# EFR32BG13_EF_Antenna_Power.net
KiCad netlist of a schematic drawn in Altium Designer
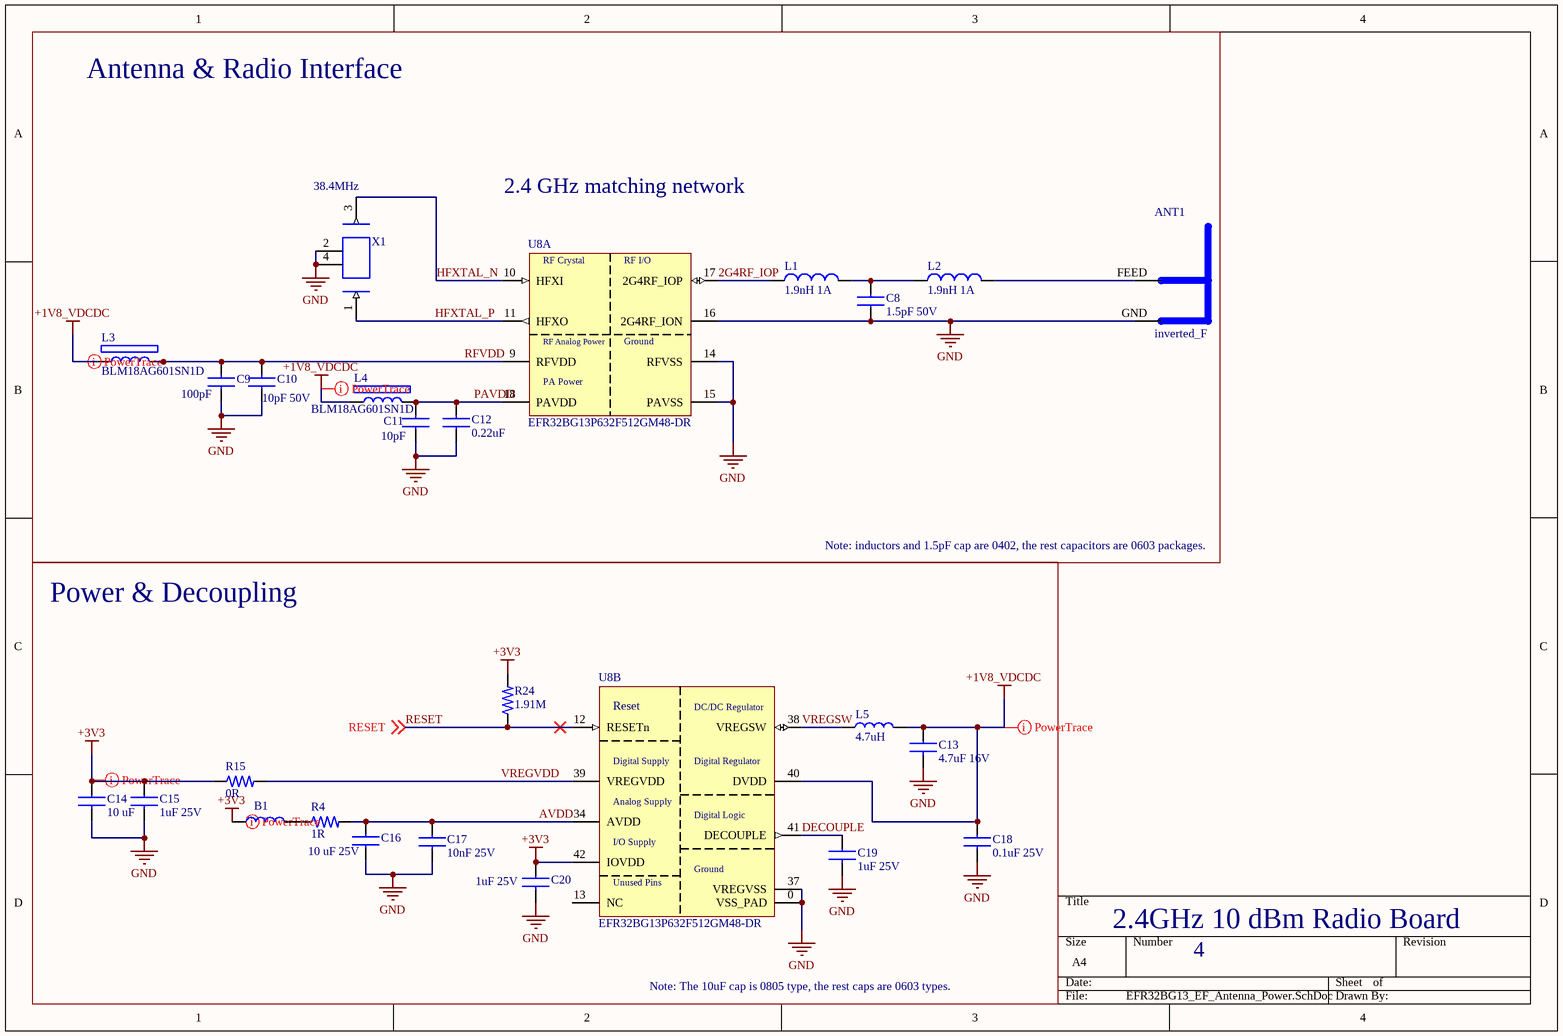
[diagram p0: EFR32BG13_EF_Antenna_Power.SchDoc]

(export (version "E")
  (design (tool "Eeschema 10.0.6"))
  (components
    (comp (ref "ANT1")
      (value "inverted_F")
      (footprint "Inverted_F_Antenna")
      (description "inverted F Antenna")
      (libsource (lib "LPEDT_Parts") (part "inverted F Antenna"))
    )
    (comp (ref "B1")
      (value "FERRITE BEAD 1K OHM 0603 1LN")
      (footprint "BEADC1608X100N")
      (description "Ferrite Beads WE-CBF 0603 SMD Bead 100MHz 1000Ohm 200mA")
      (fields
        (field (name "MANUFACTURER") "Wurth Electronics")
        (field (name "MANUFACTURER PART NUMBER") "74279266")
      )
      (libsource (lib "LPEDT_Parts") (part "74279266"))
    )
    (comp (ref "C8")
      (value "1.5pF 50V")
      (footprint "CAP_0402_1mm")
      (description "Cap Ceramic 1.5pF 50V C0G 5% Pad SMD 0402 125C Automotive T/R")
      (fields
        (field (name "MANUFACTURER") "Murata")
        (field (name "MANUFACTURER PART NUMBER") "GCM1555C1H1R5JA16D")
      )
      (libsource (lib "LPEDT_Parts") (part "GCM1555C1H1R5JA16D"))
    )
    (comp (ref "C9")
      (value "100pF")
      (footprint "Chip2Pin_1.6x0.8x0.9_CAP")
      (description "0603 100 pF 50 V ±5% Tolerance C0G SMT Multilayer Ceramic Capacitor")
      (fields
        (field (name "MANUFACTURER") "Murata")
        (field (name "MANUFACTURER PART NUMBER") "GRM1885C1H101JA01J")
      )
      (libsource (lib "LPEDT_Parts") (part "GRM1885C1H101JA01J"))
    )
    (comp (ref "C10")
      (value "10pF 50V")
      (footprint "Chip2Pin_1.6x0.8x0.9_CAP")
      (description "0603 10 pF 50 V ±5% Tolerance C0G SMT Multilayer Ceramic Capacitor")
      (fields
        (field (name "MANUFACTURER") "Murata")
        (field (name "MANUFACTURER PART NUMBER") "GRM1885C1H100JA01J")
      )
      (libsource (lib "LPEDT_Parts") (part "GRM1885C1H100JA01J"))
    )
    (comp (ref "C11")
      (value "10pF")
      (footprint "Chip2Pin_1.6x0.8x0.9_CAP")
      (description "0603 10 pF 50 V ±5% Tolerance C0G SMT Multilayer Ceramic Capacitor")
      (fields
        (field (name "MANUFACTURER") "Murata")
        (field (name "MANUFACTURER PART NUMBER") "GRM1885C1H100JA01J")
      )
      (libsource (lib "LPEDT_Parts") (part "GRM1885C1H100JA01J"))
    )
    (comp (ref "C12")
      (value "0.22uF")
      (footprint "Chip2Pin_1.6x0.8x0.9_CAP")
      (description "Cap Ceramic 0.22uF 25V X7R 10% SMD 0603 125°C Paper T/R")
      (fields
        (field (name "MANUFACTURER") "Murata")
        (field (name "MANUFACTURER PART NUMBER") "GRM188R71E224KA88J")
      )
      (libsource (lib "LPEDT_Parts") (part "GRM188R71E224KA88J"))
    )
    (comp (ref "C13")
      (value "4.7uF 16V")
      (footprint "Chip2Pin_1.6x0.8x0.9_CAP")
      (description "Cap Ceramic 4.7uF 16V X7R 10% SMD 0603 125°C Paper T/R")
      (fields
        (field (name "MANUFACTURER") "Murata")
        (field (name "MANUFACTURER PART NUMBER") "GRM188Z71C475KE21D")
      )
      (libsource (lib "LPEDT_Parts") (part "GRM188Z71C475KE21D"))
    )
    (comp (ref "C14")
      (value "10 uF")
      (footprint "GRM21BR61E106KA73K")
      (description "0805 25 V 10 uF ±20% Tolerance X5R Monolithic Ceramic Chip Capacitor")
      (fields
        (field (name "MANUFACTURER") "Murata")
        (field (name "MANUFACTURER PART NUMBER") "GRM21BR61E106KA73K")
      )
      (libsource (lib "LPEDT_Parts") (part "GRM21BR61E106KA73K"))
    )
    (comp (ref "C15")
      (value "1uF 25V")
      (footprint "Chip2Pin_1.6x0.8x0.9_CAP")
      (description "Cap Ceramic 1uF 25V X7R 10% Pad SMD 0603 125C Automotive T/R")
      (fields
        (field (name "MANUFACTURER") "Murata")
        (field (name "MANUFACTURER PART NUMBER") "GCM188R71E105KA64J")
      )
      (libsource (lib "LPEDT_Parts") (part "GCM188R71E105KA64J"))
    )
    (comp (ref "C16")
      (value "10 uF 25V")
      (footprint "GRM21BR61E106KA73K")
      (description "0805 25 V 10 uF ±20% Tolerance X5R Monolithic Ceramic Chip Capacitor")
      (fields
        (field (name "MANUFACTURER") "Murata")
        (field (name "MANUFACTURER PART NUMBER") "GRM21BR61E106KA73K")
      )
      (libsource (lib "LPEDT_Parts") (part "GRM21BR61E106KA73K"))
    )
    (comp (ref "C17")
      (value "10nF 25V")
      (footprint "Chip2Pin_1.6x0.8x0.9_CAP")
      (description "Multi-Layer Ceramic Capacitor 0.01uF 25VDC C0G 5% 0603 Paper T/R")
      (fields
        (field (name "MANUFACTURER") "Murata")
        (field (name "MANUFACTURER PART NUMBER") "GRT1885C1E103JA02J")
      )
      (libsource (lib "LPEDT_Parts") (part "GRT1885C1E103JA02J"))
    )
    (comp (ref "C18")
      (value "0.1uF 25V")
      (footprint "Chip2Pin_1.6x0.8x0.9_CAP")
      (description "Cap Ceramic 0.1uF 25V X7R 10% Pad SMD 0603 Soft Termination 125C Automotive T/R")
      (fields
        (field (name "MANUFACTURER") "Murata")
        (field (name "MANUFACTURER PART NUMBER") "GCJ188R71E104KA12D")
      )
      (libsource (lib "LPEDT_Parts") (part "GCJ188R71E104KA12D"))
    )
    (comp (ref "C19")
      (value "1uF 25V")
      (footprint "Chip2Pin_1.6x0.8x0.9_CAP")
      (description "Cap Ceramic 1uF 25V X7R 10% Pad SMD 0603 125C Automotive T/R")
      (fields
        (field (name "MANUFACTURER") "Murata")
        (field (name "MANUFACTURER PART NUMBER") "GCM188R71E105KA64J")
      )
      (libsource (lib "LPEDT_Parts") (part "GCM188R71E105KA64J"))
    )
    (comp (ref "C20")
      (value "1uF 25V")
      (footprint "Chip2Pin_1.6x0.8x0.9_CAP")
      (description "Cap Ceramic 1uF 25V X7R 10% Pad SMD 0603 125C Automotive T/R")
      (fields
        (field (name "MANUFACTURER") "Murata")
        (field (name "MANUFACTURER PART NUMBER") "GCM188R71E105KA64J")
      )
      (libsource (lib "LPEDT_Parts") (part "GCM188R71E105KA64J"))
    )
    (comp (ref "L1")
      (value "1.9nH 1A")
      (footprint "CAP_0402_1mm")
      (description "Inductor Chip 1.9nH 0.3nH Tolerance 2-Pin 0402 Paper T/R")
      (fields
        (field (name "MANUFACTURER") "Murata")
        (field (name "MANUFACTURER PART NUMBER") "LQG15WZ1N9S02D")
      )
      (libsource (lib "LPEDT_Parts") (part "LQG15WZ1N9S02D"))
    )
    (comp (ref "L2")
      (value "1.9nH 1A")
      (footprint "CAP_0402_1mm")
      (description "Inductor Chip 1.9nH 0.3nH Tolerance 2-Pin 0402 Paper T/R")
      (fields
        (field (name "MANUFACTURER") "Murata")
        (field (name "MANUFACTURER PART NUMBER") "LQG15WZ1N9S02D")
      )
      (libsource (lib "LPEDT_Parts") (part "LQG15WZ1N9S02D"))
    )
    (comp (ref "L3")
      (value "BLM18AG601SN1D")
      (footprint "Chip2Pin_1.6x0.8x0.95_ferrite")
      (description "0603 600Ω ±25% DCR=0.38Ω 500mA")
      (fields (field (name "MANUFACTURER") "Murata") (field (name "TOLERANCE") "25%"))
      (libsource (lib "LPEDT_Parts") (part "BLM18AG601SN1D"))
    )
    (comp (ref "L4")
      (value "BLM18AG601SN1D")
      (footprint "Chip2Pin_1.6x0.8x0.95_ferrite")
      (description "0603 600Ω ±25% DCR=0.38Ω 500mA")
      (fields (field (name "MANUFACTURER") "Murata") (field (name "TOLERANCE") "25%"))
      (libsource (lib "LPEDT_Parts") (part "BLM18AG601SN1D"))
    )
    (comp (ref "L5")
      (value "4.7uH")
      (footprint "IND_5050x20")
      (description "Fixed Ind 4.7UH 2.3A 55.9 Mohm")
      (fields
        (field (name "MANUFACTURER") "Wurth Electronics")
        (field (name "MANUFACTURER PART NUMBER") "74404052047")
      )
      (libsource (lib "LPEDT_Parts") (part "74404052047"))
    )
    (comp (ref "R4")
      (value "1R")
      (footprint "RES_0603_1608X06")
      (description "Res General Purpose Thick Film 0603 10 Ohm 5% 1/10W ±200ppm/°C Molded SMD Paper T/R")
      (fields
        (field (name "MANUFACTURER") "Yageo")
        (field (name "MANUFACTURER PART NUMBER") "RC0603JR-0710RL")
      )
      (libsource (lib "LPEDT_Parts") (part "RC0603JR-0710RL"))
    )
    (comp (ref "R15")
      (value "0R")
      (footprint "RES_0603_1608X06")
      (description "RC Series 0603 0.1 W 0 Ohm Jumper Surface Mount Thick Film Chip Resistor")
      (fields
        (field (name "MANUFACTURER") "Yageo")
        (field (name "MANUFACTURER PART NUMBER") "RC0603FR-070RL")
      )
      (libsource (lib "LPEDT_Parts") (part "RC0603FR-070RL"))
    )
    (comp (ref "R24")
      (value "1.91M")
      (footprint "RES_0603_1608X06")
      (description "Res Thick Film 0603 1.91M Ohm 1% 1/10W ±100ppm/°C Molded SMD SMD Paper T/R")
      (fields
        (field (name "MANUFACTURER") "Yageo")
        (field (name "MANUFACTURER PART NUMBER") "RC0603FR-071M91L")
      )
      (libsource (lib "LPEDT_Parts") (part "RC0603FR-071M91L"))
    )
    (comp (ref "U8")
      (value "EFR32BG13P632F512GM48-DR")
      (footprint "QFN_48_7X7")
      (description "Blue Gecko BLE Soc QFN48 2.4 G 10 dB BLE/Proprietary 512 kB 64 kB(RAM) 31GPIO")
      (fields (field (name "MANUFACTURER") "Silicon Labs"))
      (libsource (lib "LPEDT_Parts") (part "EFR32BG13P632F512GM48-DR"))
    )
    (comp (ref "X1")
      (value "38.4MHz")
      (footprint "OSC_38.4MHz")
      (description "Crystal 38.4000MHZ 10PF SMD")
      (fields
        (field (name "MANUFACTURER") "Raltron Electronics")
        (field (name "MANUFACTURER PART NUMBER") "RH100-38.400-10-F-1010-TR")
      )
      (libsource (lib "LPEDT_Parts") (part "RH100-38.400-10-F-1010-TR"))
    )
  )
  (nets
    (net (code "1") (name "+1V8_VDCDC") (class "Default")
      (node (ref "C13") (pin "1") (pinfunction "1_1") (pintype "passive"))
      (node (ref "C18") (pin "1") (pinfunction "1_1") (pintype "passive"))
      (node (ref "L3") (pin "1") (pinfunction "1_1") (pintype "passive"))
      (node (ref "L4") (pin "1") (pinfunction "1_1") (pintype "passive"))
      (node (ref "L5") (pin "2") (pinfunction "2_2") (pintype "passive"))
      (node (ref "U8") (pin "40") (pinfunction "DVDD_40") (pintype "power_in"))
    )
    (net (code "2") (name "+3V3") (class "Default")
      (node (ref "B1") (pin "1") (pinfunction "1_1") (pintype "passive"))
      (node (ref "C14") (pin "1") (pinfunction "1_1") (pintype "passive"))
      (node (ref "C15") (pin "1") (pinfunction "1_1") (pintype "passive"))
      (node (ref "C20") (pin "1") (pinfunction "1_1") (pintype "passive"))
      (node (ref "R15") (pin "1") (pinfunction "1_1") (pintype "passive"))
      (node (ref "R24") (pin "2") (pinfunction "2_2") (pintype "passive"))
      (node (ref "U8") (pin "42") (pinfunction "IOVDD_42") (pintype "power_in"))
    )
    (net (code "3") (name "/2G4RF_IOP") (class "Default")
      (node (ref "L1") (pin "1") (pinfunction "1_1") (pintype "passive"))
      (node (ref "U8") (pin "17") (pinfunction "2G4RF_IOP_17") (pintype "bidirectional"))
    )
    (net (code "4") (name "/AVDD") (class "Default")
      (node (ref "C16") (pin "1") (pinfunction "1_1") (pintype "passive"))
      (node (ref "C17") (pin "1") (pinfunction "1_1") (pintype "passive"))
      (node (ref "R4") (pin "2") (pinfunction "2_2") (pintype "passive"))
      (node (ref "U8") (pin "34") (pinfunction "AVDD_34") (pintype "power_in"))
    )
    (net (code "5") (name "/DECOUPLE") (class "Default")
      (node (ref "C19") (pin "1") (pinfunction "1_1") (pintype "passive"))
      (node (ref "U8") (pin "41") (pinfunction "DECOUPLE_41") (pintype "output"))
    )
    (net (code "6") (name "/HFXTAL_N") (class "Default")
      (node (ref "U8") (pin "10") (pinfunction "HFXI_10") (pintype "input"))
      (node (ref "X1") (pin "3") (pintype "output"))
    )
    (net (code "7") (name "/HFXTAL_P") (class "Default")
      (node (ref "U8") (pin "11") (pinfunction "HFXO_11") (pintype "output"))
      (node (ref "X1") (pin "1") (pintype "input"))
    )
    (net (code "8") (name "/PAVDD") (class "Default")
      (node (ref "C11") (pin "1") (pinfunction "1_1") (pintype "passive"))
      (node (ref "C12") (pin "1") (pinfunction "1_1") (pintype "passive"))
      (node (ref "L4") (pin "2") (pinfunction "2_2") (pintype "passive"))
      (node (ref "U8") (pin "18") (pinfunction "PAVDD_18") (pintype "power_in"))
    )
    (net (code "9") (name "/RFVDD") (class "Default")
      (node (ref "C10") (pin "1") (pinfunction "1_1") (pintype "passive"))
      (node (ref "C9") (pin "1") (pinfunction "1_1") (pintype "passive"))
      (node (ref "L3") (pin "2") (pinfunction "2_2") (pintype "passive"))
      (node (ref "U8") (pin "9") (pinfunction "RFVDD_9") (pintype "power_in"))
    )
    (net (code "10") (name "/VREGSW") (class "Default")
      (node (ref "L5") (pin "1") (pinfunction "1_1") (pintype "passive"))
      (node (ref "U8") (pin "38") (pinfunction "VREGSW_38") (pintype "bidirectional"))
    )
    (net (code "11") (name "/VREGVDD") (class "Default")
      (node (ref "R15") (pin "2") (pinfunction "2_2") (pintype "passive"))
      (node (ref "U8") (pin "39") (pinfunction "VREGVDD_39") (pintype "power_in"))
    )
    (net (code "12") (name "GND") (class "Default")
      (node (ref "ANT1") (pin "GND") (pinfunction "GND_GND") (pintype "passive"))
      (node (ref "C10") (pin "2") (pinfunction "2_2") (pintype "passive"))
      (node (ref "C11") (pin "2") (pinfunction "2_2") (pintype "passive"))
      (node (ref "C12") (pin "2") (pinfunction "2_2") (pintype "passive"))
      (node (ref "C13") (pin "2") (pinfunction "2_2") (pintype "passive"))
      (node (ref "C14") (pin "2") (pinfunction "2_2") (pintype "passive"))
      (node (ref "C15") (pin "2") (pinfunction "2_2") (pintype "passive"))
      (node (ref "C16") (pin "2") (pinfunction "2_2") (pintype "passive"))
      (node (ref "C17") (pin "2") (pinfunction "2_2") (pintype "passive"))
      (node (ref "C18") (pin "2") (pinfunction "2_2") (pintype "passive"))
      (node (ref "C19") (pin "2") (pinfunction "2_2") (pintype "passive"))
      (node (ref "C20") (pin "2") (pinfunction "2_2") (pintype "passive"))
      (node (ref "C8") (pin "2") (pinfunction "2_2") (pintype "passive"))
      (node (ref "C9") (pin "2") (pinfunction "2_2") (pintype "passive"))
      (node (ref "U8") (pin "0") (pinfunction "VSS_PAD_0") (pintype "passive"))
      (node (ref "U8") (pin "14") (pinfunction "RFVSS_14") (pintype "passive"))
      (node (ref "U8") (pin "15") (pinfunction "PAVSS_15") (pintype "passive"))
      (node (ref "U8") (pin "16") (pinfunction "2G4RF_ION_16") (pintype "passive"))
      (node (ref "U8") (pin "37") (pinfunction "VREGVSS_37") (pintype "passive"))
      (node (ref "X1") (pin "2") (pintype "power_in"))
      (node (ref "X1") (pin "4") (pintype "power_in"))
    )
    (net (code "13") (name "Net-(ANT1-PadFEED)") (class "Default")
      (node (ref "ANT1") (pin "FEED") (pinfunction "FEED_FEED") (pintype "passive"))
      (node (ref "L2") (pin "2") (pinfunction "2_2") (pintype "passive"))
    )
    (net (code "14") (name "Net-(B1-Pad2)") (class "Default")
      (node (ref "B1") (pin "2") (pinfunction "2_2") (pintype "passive"))
      (node (ref "R4") (pin "1") (pinfunction "1_1") (pintype "passive"))
    )
    (net (code "15") (name "Net-(C8-Pad1)") (class "Default")
      (node (ref "C8") (pin "1") (pinfunction "1_1") (pintype "passive"))
      (node (ref "L1") (pin "2") (pinfunction "2_2") (pintype "passive"))
      (node (ref "L2") (pin "1") (pinfunction "1_1") (pintype "passive"))
    )
    (net (code "16") (name "RESET") (class "Default")
      (node (ref "R24") (pin "1") (pinfunction "1_1") (pintype "passive"))
      (node (ref "U8") (pin "12") (pinfunction "RESETn_12") (pintype "input"))
    )
    (net (code "17") (name "unconnected-(U8B-NC-Pad13)") (class "Default")
      (node (ref "U8") (pin "13") (pinfunction "NC_13") (pintype "passive"))
    )
  )
)
